# EskomSePush.net
KiCad netlist of a schematic drawn in EAGLE
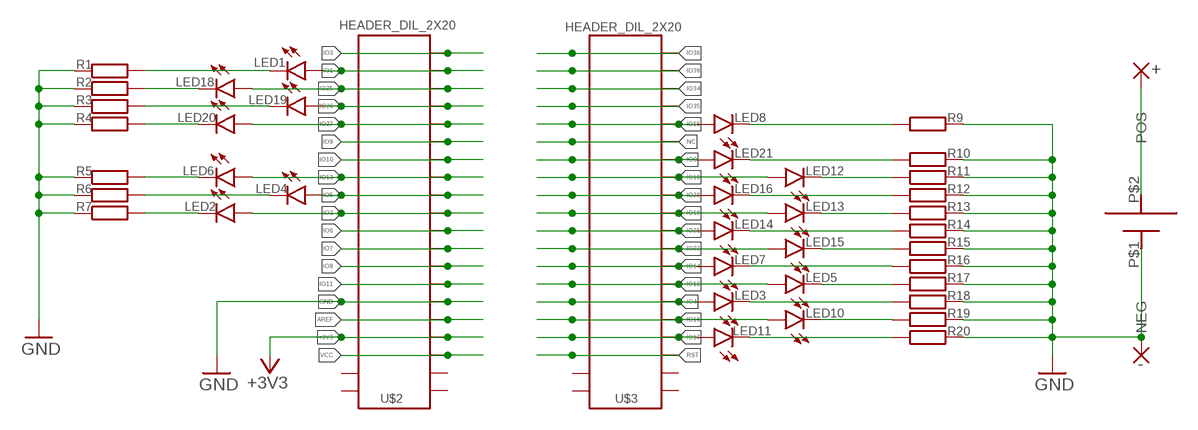
[diagram p0: schematic, sheet 1]

(export (version "E")
  (design (tool "Eeschema 10.0.6"))
  (components
    (comp (ref "+")
      (value "WIREPADSMD2,54-5,08")
      (footprint "eagle-import:SMD2,54-5,08")
      (libsource (lib "eagle-import") (part "WIREPADSMD2,54-5,08"))
    )
    (comp (ref "-")
      (value "WIREPADSMD2,54-5,08")
      (footprint "eagle-import:SMD2,54-5,08")
      (libsource (lib "eagle-import") (part "WIREPADSMD2,54-5,08"))
    )
    (comp (ref "LED1")
      (value "LEDCHIPLED_1206")
      (footprint "eagle-import:CHIPLED_1206")
      (libsource (lib "eagle-import") (part "LEDCHIPLED_1206"))
    )
    (comp (ref "LED2")
      (value "LEDCHIPLED_1206")
      (footprint "eagle-import:CHIPLED_1206")
      (libsource (lib "eagle-import") (part "LEDCHIPLED_1206"))
    )
    (comp (ref "LED3")
      (value "LEDCHIPLED_1206")
      (footprint "eagle-import:CHIPLED_1206")
      (libsource (lib "eagle-import") (part "LEDCHIPLED_1206"))
    )
    (comp (ref "LED4")
      (value "LEDCHIPLED_1206")
      (footprint "eagle-import:CHIPLED_1206")
      (libsource (lib "eagle-import") (part "LEDCHIPLED_1206"))
    )
    (comp (ref "LED5")
      (value "LEDCHIPLED_1206")
      (footprint "eagle-import:CHIPLED_1206")
      (libsource (lib "eagle-import") (part "LEDCHIPLED_1206"))
    )
    (comp (ref "LED6")
      (value "LEDCHIPLED_1206")
      (footprint "eagle-import:CHIPLED_1206")
      (libsource (lib "eagle-import") (part "LEDCHIPLED_1206"))
    )
    (comp (ref "LED7")
      (value "LEDCHIPLED_1206")
      (footprint "eagle-import:CHIPLED_1206")
      (libsource (lib "eagle-import") (part "LEDCHIPLED_1206"))
    )
    (comp (ref "LED8")
      (value "LEDCHIPLED_1206")
      (footprint "eagle-import:CHIPLED_1206")
      (libsource (lib "eagle-import") (part "LEDCHIPLED_1206"))
    )
    (comp (ref "LED10")
      (value "LEDCHIPLED_1206")
      (footprint "eagle-import:CHIPLED_1206")
      (libsource (lib "eagle-import") (part "LEDCHIPLED_1206"))
    )
    (comp (ref "LED11")
      (value "LEDCHIPLED_1206")
      (footprint "eagle-import:CHIPLED_1206")
      (libsource (lib "eagle-import") (part "LEDCHIPLED_1206"))
    )
    (comp (ref "LED12")
      (value "LEDCHIPLED_1206")
      (footprint "eagle-import:CHIPLED_1206")
      (libsource (lib "eagle-import") (part "LEDCHIPLED_1206"))
    )
    (comp (ref "LED13")
      (value "LEDCHIPLED_1206")
      (footprint "eagle-import:CHIPLED_1206")
      (libsource (lib "eagle-import") (part "LEDCHIPLED_1206"))
    )
    (comp (ref "LED14")
      (value "LEDCHIPLED_1206")
      (footprint "eagle-import:CHIPLED_1206")
      (libsource (lib "eagle-import") (part "LEDCHIPLED_1206"))
    )
    (comp (ref "LED15")
      (value "LEDCHIPLED_1206")
      (footprint "eagle-import:CHIPLED_1206")
      (libsource (lib "eagle-import") (part "LEDCHIPLED_1206"))
    )
    (comp (ref "LED16")
      (value "LEDCHIPLED_1206")
      (footprint "eagle-import:CHIPLED_1206")
      (libsource (lib "eagle-import") (part "LEDCHIPLED_1206"))
    )
    (comp (ref "LED18")
      (value "LEDCHIPLED_1206")
      (footprint "eagle-import:CHIPLED_1206")
      (libsource (lib "eagle-import") (part "LEDCHIPLED_1206"))
    )
    (comp (ref "LED19")
      (value "LEDCHIPLED_1206")
      (footprint "eagle-import:CHIPLED_1206")
      (libsource (lib "eagle-import") (part "LEDCHIPLED_1206"))
    )
    (comp (ref "LED20")
      (value "LEDCHIPLED_1206")
      (footprint "eagle-import:CHIPLED_1206")
      (libsource (lib "eagle-import") (part "LEDCHIPLED_1206"))
    )
    (comp (ref "LED21")
      (value "LEDCHIPLED_1206")
      (footprint "eagle-import:CHIPLED_1206")
      (libsource (lib "eagle-import") (part "LEDCHIPLED_1206"))
    )
    (comp (ref "R1")
      (value "R-EU_R1206")
      (footprint "eagle-import:R1206")
      (libsource (lib "eagle-import") (part "R-EU_R1206"))
    )
    (comp (ref "R2")
      (value "R-EU_R1206")
      (footprint "eagle-import:R1206")
      (libsource (lib "eagle-import") (part "R-EU_R1206"))
    )
    (comp (ref "R3")
      (value "R-EU_R1206")
      (footprint "eagle-import:R1206")
      (libsource (lib "eagle-import") (part "R-EU_R1206"))
    )
    (comp (ref "R4")
      (value "R-EU_R1206")
      (footprint "eagle-import:R1206")
      (libsource (lib "eagle-import") (part "R-EU_R1206"))
    )
    (comp (ref "R5")
      (value "R-EU_R1206")
      (footprint "eagle-import:R1206")
      (libsource (lib "eagle-import") (part "R-EU_R1206"))
    )
    (comp (ref "R6")
      (value "R-EU_R1206")
      (footprint "eagle-import:R1206")
      (libsource (lib "eagle-import") (part "R-EU_R1206"))
    )
    (comp (ref "R7")
      (value "R-EU_R1206")
      (footprint "eagle-import:R1206")
      (libsource (lib "eagle-import") (part "R-EU_R1206"))
    )
    (comp (ref "R9")
      (value "R-EU_R1206")
      (footprint "eagle-import:R1206")
      (libsource (lib "eagle-import") (part "R-EU_R1206"))
    )
    (comp (ref "R10")
      (value "R-EU_R1206")
      (footprint "eagle-import:R1206")
      (libsource (lib "eagle-import") (part "R-EU_R1206"))
    )
    (comp (ref "R11")
      (value "R-EU_R1206")
      (footprint "eagle-import:R1206")
      (libsource (lib "eagle-import") (part "R-EU_R1206"))
    )
    (comp (ref "R12")
      (value "R-EU_R1206")
      (footprint "eagle-import:R1206")
      (libsource (lib "eagle-import") (part "R-EU_R1206"))
    )
    (comp (ref "R13")
      (value "R-EU_R1206")
      (footprint "eagle-import:R1206")
      (libsource (lib "eagle-import") (part "R-EU_R1206"))
    )
    (comp (ref "R14")
      (value "R-EU_R1206")
      (footprint "eagle-import:R1206")
      (libsource (lib "eagle-import") (part "R-EU_R1206"))
    )
    (comp (ref "R15")
      (value "R-EU_R1206")
      (footprint "eagle-import:R1206")
      (libsource (lib "eagle-import") (part "R-EU_R1206"))
    )
    (comp (ref "R16")
      (value "R-EU_R1206")
      (footprint "eagle-import:R1206")
      (libsource (lib "eagle-import") (part "R-EU_R1206"))
    )
    (comp (ref "R17")
      (value "R-EU_R1206")
      (footprint "eagle-import:R1206")
      (libsource (lib "eagle-import") (part "R-EU_R1206"))
    )
    (comp (ref "R18")
      (value "R-EU_R1206")
      (footprint "eagle-import:R1206")
      (libsource (lib "eagle-import") (part "R-EU_R1206"))
    )
    (comp (ref "R19")
      (value "R-EU_R1206")
      (footprint "eagle-import:R1206")
      (libsource (lib "eagle-import") (part "R-EU_R1206"))
    )
    (comp (ref "R20")
      (value "R-EU_R1206")
      (footprint "eagle-import:R1206")
      (libsource (lib "eagle-import") (part "R-EU_R1206"))
    )
    (comp (ref "U$1")
      (value "21700BATTERYHOLDER")
      (footprint "eagle-import:21700BATTERYHOLDER")
      (libsource (lib "eagle-import") (part "21700BATTERYHOLDER"))
    )
    (comp (ref "U$2")
      (value "HEADER_DIL_2X20")
      (footprint "eagle-import:HEADER_DIL_2X20")
      (libsource (lib "eagle-import") (part "HEADER_DIL_2X20"))
    )
    (comp (ref "U$3")
      (value "HEADER_DIL_2X20")
      (footprint "eagle-import:HEADER_DIL_2X20")
      (libsource (lib "eagle-import") (part "HEADER_DIL_2X20"))
    )
  )
  (nets
    (net (code "1") (name "+3V3") (class "Default")
      (node (ref "U$2") (pin "P$17") (pinfunction "P$17_P$17") (pintype "bidirectional"))
      (node (ref "U$2") (pin "P$37") (pinfunction "P$37_P$37") (pintype "bidirectional"))
    )
    (net (code "2") (name "AREF") (class "Default")
      (node (ref "U$2") (pin "P$16") (pinfunction "P$16_P$16") (pintype "bidirectional"))
      (node (ref "U$2") (pin "P$36") (pinfunction "P$36_P$36") (pintype "bidirectional"))
    )
    (net (code "3") (name "GND") (class "Default")
      (node (ref "-") (pin "1") (pinfunction "P_1") (pintype "passive"))
      (node (ref "R1") (pin "1") (pinfunction "1_1") (pintype "passive"))
      (node (ref "R10") (pin "2") (pinfunction "2_2") (pintype "passive"))
      (node (ref "R11") (pin "2") (pinfunction "2_2") (pintype "passive"))
      (node (ref "R12") (pin "2") (pinfunction "2_2") (pintype "passive"))
      (node (ref "R13") (pin "2") (pinfunction "2_2") (pintype "passive"))
      (node (ref "R14") (pin "2") (pinfunction "2_2") (pintype "passive"))
      (node (ref "R15") (pin "2") (pinfunction "2_2") (pintype "passive"))
      (node (ref "R16") (pin "2") (pinfunction "2_2") (pintype "passive"))
      (node (ref "R17") (pin "2") (pinfunction "2_2") (pintype "passive"))
      (node (ref "R18") (pin "2") (pinfunction "2_2") (pintype "passive"))
      (node (ref "R19") (pin "2") (pinfunction "2_2") (pintype "passive"))
      (node (ref "R2") (pin "1") (pinfunction "1_1") (pintype "passive"))
      (node (ref "R20") (pin "2") (pinfunction "2_2") (pintype "passive"))
      (node (ref "R3") (pin "1") (pinfunction "1_1") (pintype "passive"))
      (node (ref "R4") (pin "1") (pinfunction "1_1") (pintype "passive"))
      (node (ref "R5") (pin "1") (pinfunction "1_1") (pintype "passive"))
      (node (ref "R6") (pin "1") (pinfunction "1_1") (pintype "passive"))
      (node (ref "R7") (pin "1") (pinfunction "1_1") (pintype "passive"))
      (node (ref "R9") (pin "2") (pinfunction "2_2") (pintype "passive"))
      (node (ref "U$1") (pin "P$1") (pinfunction "NEG_P$1") (pintype "bidirectional"))
      (node (ref "U$2") (pin "P$15") (pinfunction "P$15_P$15") (pintype "bidirectional"))
      (node (ref "U$2") (pin "P$35") (pinfunction "P$35_P$35") (pintype "bidirectional"))
    )
    (net (code "4") (name "IO0") (class "Default")
      (node (ref "LED21") (pin "A") (pinfunction "A_A") (pintype "passive"))
      (node (ref "U$3") (pin "P$27") (pinfunction "P$27_P$27") (pintype "bidirectional"))
      (node (ref "U$3") (pin "P$7") (pinfunction "P$7_P$7") (pintype "bidirectional"))
    )
    (net (code "5") (name "IO1") (class "Default")
      (node (ref "LED1") (pin "A") (pinfunction "A_A") (pintype "passive"))
      (node (ref "U$2") (pin "P$2") (pinfunction "P$2_P$2") (pintype "bidirectional"))
      (node (ref "U$2") (pin "P$22") (pinfunction "P$22_P$22") (pintype "bidirectional"))
    )
    (net (code "6") (name "IO2") (class "Default")
      (node (ref "LED2") (pin "A") (pinfunction "A_A") (pintype "passive"))
      (node (ref "U$2") (pin "P$10") (pinfunction "P$10_P$10") (pintype "bidirectional"))
      (node (ref "U$2") (pin "P$30") (pinfunction "P$30_P$30") (pintype "bidirectional"))
    )
    (net (code "7") (name "IO3") (class "Default")
      (node (ref "U$2") (pin "P$1") (pinfunction "P$1_P$1") (pintype "bidirectional"))
      (node (ref "U$2") (pin "P$21") (pinfunction "P$21_P$21") (pintype "bidirectional"))
    )
    (net (code "8") (name "IO4") (class "Default")
      (node (ref "LED3") (pin "A") (pinfunction "A_A") (pintype "passive"))
      (node (ref "U$3") (pin "P$15") (pinfunction "P$15_P$15") (pintype "bidirectional"))
      (node (ref "U$3") (pin "P$35") (pinfunction "P$35_P$35") (pintype "bidirectional"))
    )
    (net (code "9") (name "IO5") (class "Default")
      (node (ref "LED4") (pin "A") (pinfunction "A_A") (pintype "passive"))
      (node (ref "U$2") (pin "P$29") (pinfunction "P$29_P$29") (pintype "bidirectional"))
      (node (ref "U$2") (pin "P$9") (pinfunction "P$9_P$9") (pintype "bidirectional"))
    )
    (net (code "10") (name "IO6") (class "Default")
      (node (ref "U$2") (pin "P$11") (pinfunction "P$11_P$11") (pintype "bidirectional"))
      (node (ref "U$2") (pin "P$31") (pinfunction "P$31_P$31") (pintype "bidirectional"))
    )
    (net (code "11") (name "IO7") (class "Default")
      (node (ref "U$2") (pin "P$12") (pinfunction "P$12_P$12") (pintype "bidirectional"))
      (node (ref "U$2") (pin "P$32") (pinfunction "P$32_P$32") (pintype "bidirectional"))
    )
    (net (code "12") (name "IO8") (class "Default")
      (node (ref "U$2") (pin "P$13") (pinfunction "P$13_P$13") (pintype "bidirectional"))
      (node (ref "U$2") (pin "P$33") (pinfunction "P$33_P$33") (pintype "bidirectional"))
    )
    (net (code "13") (name "IO9") (class "Default")
      (node (ref "U$2") (pin "P$26") (pinfunction "P$26_P$26") (pintype "bidirectional"))
      (node (ref "U$2") (pin "P$6") (pinfunction "P$6_P$6") (pintype "bidirectional"))
    )
    (net (code "14") (name "IO10") (class "Default")
      (node (ref "U$2") (pin "P$27") (pinfunction "P$27_P$27") (pintype "bidirectional"))
      (node (ref "U$2") (pin "P$7") (pinfunction "P$7_P$7") (pintype "bidirectional"))
    )
    (net (code "15") (name "IO11") (class "Default")
      (node (ref "U$2") (pin "P$14") (pinfunction "P$14_P$14") (pintype "bidirectional"))
      (node (ref "U$2") (pin "P$34") (pinfunction "P$34_P$34") (pintype "bidirectional"))
    )
    (net (code "16") (name "IO12") (class "Default")
      (node (ref "LED5") (pin "A") (pinfunction "A_A") (pintype "passive"))
      (node (ref "U$3") (pin "P$14") (pinfunction "P$14_P$14") (pintype "bidirectional"))
      (node (ref "U$3") (pin "P$34") (pinfunction "P$34_P$34") (pintype "bidirectional"))
    )
    (net (code "17") (name "IO13") (class "Default")
      (node (ref "LED6") (pin "A") (pinfunction "A_A") (pintype "passive"))
      (node (ref "U$2") (pin "P$28") (pinfunction "P$28_P$28") (pintype "bidirectional"))
      (node (ref "U$2") (pin "P$8") (pinfunction "P$8_P$8") (pintype "bidirectional"))
    )
    (net (code "18") (name "IO14") (class "Default")
      (node (ref "LED7") (pin "A") (pinfunction "A_A") (pintype "passive"))
      (node (ref "U$3") (pin "P$13") (pinfunction "P$13_P$13") (pintype "bidirectional"))
      (node (ref "U$3") (pin "P$33") (pinfunction "P$33_P$33") (pintype "bidirectional"))
    )
    (net (code "19") (name "IO15") (class "Default")
      (node (ref "LED8") (pin "A") (pinfunction "A_A") (pintype "passive"))
      (node (ref "U$3") (pin "P$25") (pinfunction "P$25_P$25") (pintype "bidirectional"))
      (node (ref "U$3") (pin "P$5") (pinfunction "P$5_P$5") (pintype "bidirectional"))
    )
    (net (code "20") (name "IO16") (class "Default")
      (node (ref "LED10") (pin "A") (pinfunction "A_A") (pintype "passive"))
      (node (ref "U$3") (pin "P$16") (pinfunction "P$16_P$16") (pintype "bidirectional"))
      (node (ref "U$3") (pin "P$36") (pinfunction "P$36_P$36") (pintype "bidirectional"))
    )
    (net (code "21") (name "IO17") (class "Default")
      (node (ref "LED11") (pin "A") (pinfunction "A_A") (pintype "passive"))
      (node (ref "U$3") (pin "P$17") (pinfunction "P$17_P$17") (pintype "bidirectional"))
      (node (ref "U$3") (pin "P$37") (pinfunction "P$37_P$37") (pintype "bidirectional"))
    )
    (net (code "22") (name "IO18") (class "Default")
      (node (ref "LED12") (pin "A") (pinfunction "A_A") (pintype "passive"))
      (node (ref "U$3") (pin "P$28") (pinfunction "P$28_P$28") (pintype "bidirectional"))
      (node (ref "U$3") (pin "P$8") (pinfunction "P$8_P$8") (pintype "bidirectional"))
    )
    (net (code "23") (name "IO19") (class "Default")
      (node (ref "LED13") (pin "A") (pinfunction "A_A") (pintype "passive"))
      (node (ref "U$3") (pin "P$10") (pinfunction "P$10_P$10") (pintype "bidirectional"))
      (node (ref "U$3") (pin "P$30") (pinfunction "P$30_P$30") (pintype "bidirectional"))
    )
    (net (code "24") (name "IO21") (class "Default")
      (node (ref "LED14") (pin "A") (pinfunction "A_A") (pintype "passive"))
      (node (ref "U$3") (pin "P$11") (pinfunction "P$11_P$11") (pintype "bidirectional"))
      (node (ref "U$3") (pin "P$31") (pinfunction "P$31_P$31") (pintype "bidirectional"))
    )
    (net (code "25") (name "IO22") (class "Default")
      (node (ref "LED15") (pin "A") (pinfunction "A_A") (pintype "passive"))
      (node (ref "U$3") (pin "P$12") (pinfunction "P$12_P$12") (pintype "bidirectional"))
      (node (ref "U$3") (pin "P$32") (pinfunction "P$32_P$32") (pintype "bidirectional"))
    )
    (net (code "26") (name "IO23") (class "Default")
      (node (ref "LED16") (pin "A") (pinfunction "A_A") (pintype "passive"))
      (node (ref "U$3") (pin "P$29") (pinfunction "P$29_P$29") (pintype "bidirectional"))
      (node (ref "U$3") (pin "P$9") (pinfunction "P$9_P$9") (pintype "bidirectional"))
    )
    (net (code "27") (name "IO25") (class "Default")
      (node (ref "LED18") (pin "A") (pinfunction "A_A") (pintype "passive"))
      (node (ref "U$2") (pin "P$23") (pinfunction "P$23_P$23") (pintype "bidirectional"))
      (node (ref "U$2") (pin "P$3") (pinfunction "P$3_P$3") (pintype "bidirectional"))
    )
    (net (code "28") (name "IO26") (class "Default")
      (node (ref "LED19") (pin "A") (pinfunction "A_A") (pintype "passive"))
      (node (ref "U$2") (pin "P$24") (pinfunction "P$24_P$24") (pintype "bidirectional"))
      (node (ref "U$2") (pin "P$4") (pinfunction "P$4_P$4") (pintype "bidirectional"))
    )
    (net (code "29") (name "IO27") (class "Default")
      (node (ref "LED20") (pin "A") (pinfunction "A_A") (pintype "passive"))
      (node (ref "U$2") (pin "P$25") (pinfunction "P$25_P$25") (pintype "bidirectional"))
      (node (ref "U$2") (pin "P$5") (pinfunction "P$5_P$5") (pintype "bidirectional"))
    )
    (net (code "30") (name "IO34") (class "Default")
      (node (ref "U$3") (pin "P$23") (pinfunction "P$23_P$23") (pintype "bidirectional"))
      (node (ref "U$3") (pin "P$3") (pinfunction "P$3_P$3") (pintype "bidirectional"))
    )
    (net (code "31") (name "IO35") (class "Default")
      (node (ref "U$3") (pin "P$24") (pinfunction "P$24_P$24") (pintype "bidirectional"))
      (node (ref "U$3") (pin "P$4") (pinfunction "P$4_P$4") (pintype "bidirectional"))
    )
    (net (code "32") (name "IO36") (class "Default")
      (node (ref "U$3") (pin "P$1") (pinfunction "P$1_P$1") (pintype "bidirectional"))
      (node (ref "U$3") (pin "P$21") (pinfunction "P$21_P$21") (pintype "bidirectional"))
    )
    (net (code "33") (name "IO39") (class "Default")
      (node (ref "U$3") (pin "P$2") (pinfunction "P$2_P$2") (pintype "bidirectional"))
      (node (ref "U$3") (pin "P$22") (pinfunction "P$22_P$22") (pintype "bidirectional"))
    )
    (net (code "34") (name "NC") (class "Default")
      (node (ref "U$3") (pin "P$26") (pinfunction "P$26_P$26") (pintype "bidirectional"))
      (node (ref "U$3") (pin "P$6") (pinfunction "P$6_P$6") (pintype "bidirectional"))
    )
    (net (code "35") (name "Net-(+-P)") (class "Default")
      (node (ref "+") (pin "1") (pinfunction "P_1") (pintype "passive"))
      (node (ref "U$1") (pin "P$2") (pinfunction "POS_P$2") (pintype "bidirectional"))
    )
    (net (code "36") (name "Net-(LED1-PadC)") (class "Default")
      (node (ref "LED1") (pin "C") (pinfunction "C_C") (pintype "passive"))
      (node (ref "R1") (pin "2") (pinfunction "2_2") (pintype "passive"))
    )
    (net (code "37") (name "Net-(LED2-PadC)") (class "Default")
      (node (ref "LED2") (pin "C") (pinfunction "C_C") (pintype "passive"))
      (node (ref "R7") (pin "2") (pinfunction "2_2") (pintype "passive"))
    )
    (net (code "38") (name "Net-(LED3-PadC)") (class "Default")
      (node (ref "LED3") (pin "C") (pinfunction "C_C") (pintype "passive"))
      (node (ref "R18") (pin "1") (pinfunction "1_1") (pintype "passive"))
    )
    (net (code "39") (name "Net-(LED4-PadC)") (class "Default")
      (node (ref "LED4") (pin "C") (pinfunction "C_C") (pintype "passive"))
      (node (ref "R6") (pin "2") (pinfunction "2_2") (pintype "passive"))
    )
    (net (code "40") (name "Net-(LED5-PadC)") (class "Default")
      (node (ref "LED5") (pin "C") (pinfunction "C_C") (pintype "passive"))
      (node (ref "R17") (pin "1") (pinfunction "1_1") (pintype "passive"))
    )
    (net (code "41") (name "Net-(LED6-PadC)") (class "Default")
      (node (ref "LED6") (pin "C") (pinfunction "C_C") (pintype "passive"))
      (node (ref "R5") (pin "2") (pinfunction "2_2") (pintype "passive"))
    )
    (net (code "42") (name "Net-(LED7-PadC)") (class "Default")
      (node (ref "LED7") (pin "C") (pinfunction "C_C") (pintype "passive"))
      (node (ref "R16") (pin "1") (pinfunction "1_1") (pintype "passive"))
    )
    (net (code "43") (name "Net-(LED8-PadC)") (class "Default")
      (node (ref "LED8") (pin "C") (pinfunction "C_C") (pintype "passive"))
      (node (ref "R9") (pin "1") (pinfunction "1_1") (pintype "passive"))
    )
    (net (code "44") (name "Net-(LED10-PadC)") (class "Default")
      (node (ref "LED10") (pin "C") (pinfunction "C_C") (pintype "passive"))
      (node (ref "R19") (pin "1") (pinfunction "1_1") (pintype "passive"))
    )
    (net (code "45") (name "Net-(LED11-PadC)") (class "Default")
      (node (ref "LED11") (pin "C") (pinfunction "C_C") (pintype "passive"))
      (node (ref "R20") (pin "1") (pinfunction "1_1") (pintype "passive"))
    )
    (net (code "46") (name "Net-(LED12-PadC)") (class "Default")
      (node (ref "LED12") (pin "C") (pinfunction "C_C") (pintype "passive"))
      (node (ref "R11") (pin "1") (pinfunction "1_1") (pintype "passive"))
    )
    (net (code "47") (name "Net-(LED13-PadC)") (class "Default")
      (node (ref "LED13") (pin "C") (pinfunction "C_C") (pintype "passive"))
      (node (ref "R13") (pin "1") (pinfunction "1_1") (pintype "passive"))
    )
    (net (code "48") (name "Net-(LED14-PadC)") (class "Default")
      (node (ref "LED14") (pin "C") (pinfunction "C_C") (pintype "passive"))
      (node (ref "R14") (pin "1") (pinfunction "1_1") (pintype "passive"))
    )
    (net (code "49") (name "Net-(LED15-PadC)") (class "Default")
      (node (ref "LED15") (pin "C") (pinfunction "C_C") (pintype "passive"))
      (node (ref "R15") (pin "1") (pinfunction "1_1") (pintype "passive"))
    )
    (net (code "50") (name "Net-(LED16-PadC)") (class "Default")
      (node (ref "LED16") (pin "C") (pinfunction "C_C") (pintype "passive"))
      (node (ref "R12") (pin "1") (pinfunction "1_1") (pintype "passive"))
    )
    (net (code "51") (name "Net-(LED18-PadC)") (class "Default")
      (node (ref "LED18") (pin "C") (pinfunction "C_C") (pintype "passive"))
      (node (ref "R2") (pin "2") (pinfunction "2_2") (pintype "passive"))
    )
    (net (code "52") (name "Net-(LED19-PadC)") (class "Default")
      (node (ref "LED19") (pin "C") (pinfunction "C_C") (pintype "passive"))
      (node (ref "R3") (pin "2") (pinfunction "2_2") (pintype "passive"))
    )
    (net (code "53") (name "Net-(LED20-PadC)") (class "Default")
      (node (ref "LED20") (pin "C") (pinfunction "C_C") (pintype "passive"))
      (node (ref "R4") (pin "2") (pinfunction "2_2") (pintype "passive"))
    )
    (net (code "54") (name "Net-(LED21-PadC)") (class "Default")
      (node (ref "LED21") (pin "C") (pinfunction "C_C") (pintype "passive"))
      (node (ref "R10") (pin "1") (pinfunction "1_1") (pintype "passive"))
    )
    (net (code "55") (name "RST") (class "Default")
      (node (ref "U$3") (pin "P$18") (pinfunction "P$18_P$18") (pintype "bidirectional"))
      (node (ref "U$3") (pin "P$38") (pinfunction "P$38_P$38") (pintype "bidirectional"))
    )
    (net (code "56") (name "VCC") (class "Default")
      (node (ref "U$2") (pin "P$18") (pinfunction "P$18_P$18") (pintype "bidirectional"))
      (node (ref "U$2") (pin "P$38") (pinfunction "P$38_P$38") (pintype "bidirectional"))
    )
    (net (code "57") (name "unconnected-(U$2-PadP$19)") (class "Default")
      (node (ref "U$2") (pin "P$19") (pinfunction "P$19_P$19") (pintype "bidirectional"))
    )
    (net (code "58") (name "unconnected-(U$2-PadP$20)") (class "Default")
      (node (ref "U$2") (pin "P$20") (pinfunction "P$20_P$20") (pintype "bidirectional"))
    )
    (net (code "59") (name "unconnected-(U$2-PadP$39)") (class "Default")
      (node (ref "U$2") (pin "P$39") (pinfunction "P$39_P$39") (pintype "bidirectional"))
    )
    (net (code "60") (name "unconnected-(U$2-PadP$40)") (class "Default")
      (node (ref "U$2") (pin "P$40") (pinfunction "P$40_P$40") (pintype "bidirectional"))
    )
    (net (code "61") (name "unconnected-(U$3-PadP$19)") (class "Default")
      (node (ref "U$3") (pin "P$19") (pinfunction "P$19_P$19") (pintype "bidirectional"))
    )
    (net (code "62") (name "unconnected-(U$3-PadP$20)") (class "Default")
      (node (ref "U$3") (pin "P$20") (pinfunction "P$20_P$20") (pintype "bidirectional"))
    )
    (net (code "63") (name "unconnected-(U$3-PadP$39)") (class "Default")
      (node (ref "U$3") (pin "P$39") (pinfunction "P$39_P$39") (pintype "bidirectional"))
    )
    (net (code "64") (name "unconnected-(U$3-PadP$40)") (class "Default")
      (node (ref "U$3") (pin "P$40") (pinfunction "P$40_P$40") (pintype "bidirectional"))
    )
  )
)
